# R202E.net
KiCad netlist of a schematic drawn in EAGLE
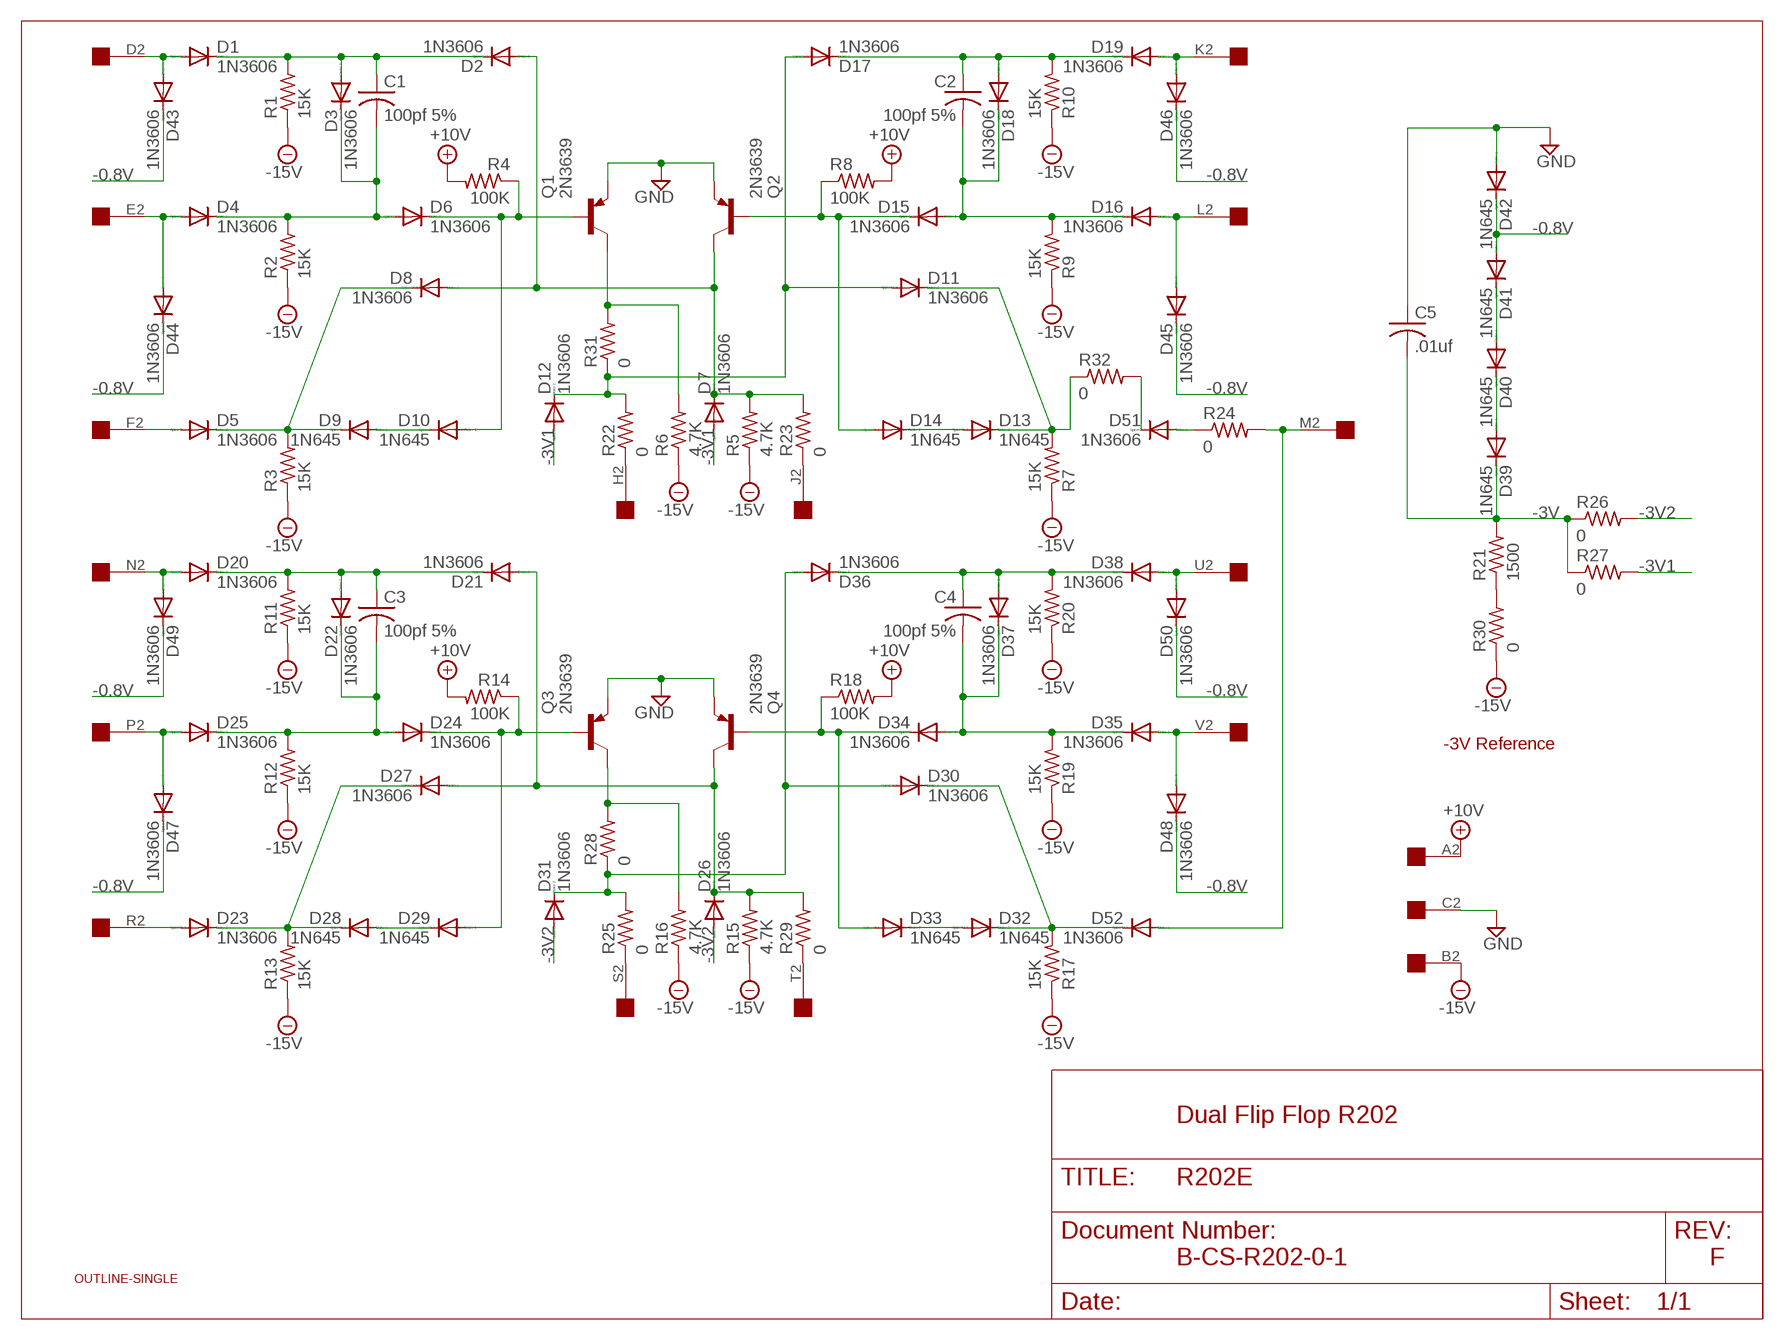
[diagram p0: schematic, sheet 1]

(export (version "E")
  (design (tool "Eeschema 10.0.6"))
  (components
    (comp (ref "C1")
      (value "100pf 5%")
      (footprint "eagle-import:C050-025X075")
      (libsource (lib "eagle-import") (part "C-US050-025X075"))
    )
    (comp (ref "C2")
      (value "100pf 5%")
      (footprint "eagle-import:C050-025X075")
      (libsource (lib "eagle-import") (part "C-US050-025X075"))
    )
    (comp (ref "C3")
      (value "100pf 5%")
      (footprint "eagle-import:C050-025X075")
      (libsource (lib "eagle-import") (part "C-US050-025X075"))
    )
    (comp (ref "C4")
      (value "100pf 5%")
      (footprint "eagle-import:C050-025X075")
      (libsource (lib "eagle-import") (part "C-US050-025X075"))
    )
    (comp (ref "C5")
      (value ".01uf")
      (footprint "eagle-import:C050-025X075")
      (libsource (lib "eagle-import") (part "C-US050-025X075"))
    )
    (comp (ref "D1")
      (value "1N3606")
      (footprint "eagle-import:DO35-10")
      (libsource (lib "eagle-import") (part "1N4148DO35-10"))
    )
    (comp (ref "D2")
      (value "1N3606")
      (footprint "eagle-import:DO35-10")
      (libsource (lib "eagle-import") (part "1N4148DO35-10"))
    )
    (comp (ref "D3")
      (value "1N3606")
      (footprint "eagle-import:DO35-10")
      (libsource (lib "eagle-import") (part "1N4148DO35-10"))
    )
    (comp (ref "D4")
      (value "1N3606")
      (footprint "eagle-import:DO35-10")
      (libsource (lib "eagle-import") (part "1N4148DO35-10"))
    )
    (comp (ref "D5")
      (value "1N3606")
      (footprint "eagle-import:DO35-10")
      (libsource (lib "eagle-import") (part "1N4148DO35-10"))
    )
    (comp (ref "D6")
      (value "1N3606")
      (footprint "eagle-import:DO35-10")
      (libsource (lib "eagle-import") (part "1N4148DO35-10"))
    )
    (comp (ref "D7")
      (value "1N3606")
      (footprint "eagle-import:DO35-10")
      (libsource (lib "eagle-import") (part "1N4148DO35-10"))
    )
    (comp (ref "D8")
      (value "1N3606")
      (footprint "eagle-import:DO35-10")
      (libsource (lib "eagle-import") (part "1N4148DO35-10"))
    )
    (comp (ref "D9")
      (value "1N645")
      (footprint "eagle-import:DO35-10")
      (libsource (lib "eagle-import") (part "1N4148DO35-10"))
    )
    (comp (ref "D10")
      (value "1N645")
      (footprint "eagle-import:DO35-10")
      (libsource (lib "eagle-import") (part "1N4148DO35-10"))
    )
    (comp (ref "D11")
      (value "1N3606")
      (footprint "eagle-import:DO35-10")
      (libsource (lib "eagle-import") (part "1N4148DO35-10"))
    )
    (comp (ref "D12")
      (value "1N3606")
      (footprint "eagle-import:DO35-10")
      (libsource (lib "eagle-import") (part "1N4148DO35-10"))
    )
    (comp (ref "D13")
      (value "1N645")
      (footprint "eagle-import:DO35-10")
      (libsource (lib "eagle-import") (part "1N4148DO35-10"))
    )
    (comp (ref "D14")
      (value "1N645")
      (footprint "eagle-import:DO35-10")
      (libsource (lib "eagle-import") (part "1N4148DO35-10"))
    )
    (comp (ref "D15")
      (value "1N3606")
      (footprint "eagle-import:DO35-10")
      (libsource (lib "eagle-import") (part "1N4148DO35-10"))
    )
    (comp (ref "D16")
      (value "1N3606")
      (footprint "eagle-import:DO35-10")
      (libsource (lib "eagle-import") (part "1N4148DO35-10"))
    )
    (comp (ref "D17")
      (value "1N3606")
      (footprint "eagle-import:DO35-10")
      (libsource (lib "eagle-import") (part "1N4148DO35-10"))
    )
    (comp (ref "D18")
      (value "1N3606")
      (footprint "eagle-import:DO35-10")
      (libsource (lib "eagle-import") (part "1N4148DO35-10"))
    )
    (comp (ref "D19")
      (value "1N3606")
      (footprint "eagle-import:DO35-10")
      (libsource (lib "eagle-import") (part "1N4148DO35-10"))
    )
    (comp (ref "D20")
      (value "1N3606")
      (footprint "eagle-import:DO35-10")
      (libsource (lib "eagle-import") (part "1N4148DO35-10"))
    )
    (comp (ref "D21")
      (value "1N3606")
      (footprint "eagle-import:DO35-10")
      (libsource (lib "eagle-import") (part "1N4148DO35-10"))
    )
    (comp (ref "D22")
      (value "1N3606")
      (footprint "eagle-import:DO35-10")
      (libsource (lib "eagle-import") (part "1N4148DO35-10"))
    )
    (comp (ref "D23")
      (value "1N3606")
      (footprint "eagle-import:DO35-10")
      (libsource (lib "eagle-import") (part "1N4148DO35-10"))
    )
    (comp (ref "D24")
      (value "1N3606")
      (footprint "eagle-import:DO35-10")
      (libsource (lib "eagle-import") (part "1N4148DO35-10"))
    )
    (comp (ref "D25")
      (value "1N3606")
      (footprint "eagle-import:DO35-10")
      (libsource (lib "eagle-import") (part "1N4148DO35-10"))
    )
    (comp (ref "D26")
      (value "1N3606")
      (footprint "eagle-import:DO35-10")
      (libsource (lib "eagle-import") (part "1N4148DO35-10"))
    )
    (comp (ref "D27")
      (value "1N3606")
      (footprint "eagle-import:DO35-10")
      (libsource (lib "eagle-import") (part "1N4148DO35-10"))
    )
    (comp (ref "D28")
      (value "1N645")
      (footprint "eagle-import:DO35-10")
      (libsource (lib "eagle-import") (part "1N4148DO35-10"))
    )
    (comp (ref "D29")
      (value "1N645")
      (footprint "eagle-import:DO35-10")
      (libsource (lib "eagle-import") (part "1N4148DO35-10"))
    )
    (comp (ref "D30")
      (value "1N3606")
      (footprint "eagle-import:DO35-10")
      (libsource (lib "eagle-import") (part "1N4148DO35-10"))
    )
    (comp (ref "D31")
      (value "1N3606")
      (footprint "eagle-import:DO35-10")
      (libsource (lib "eagle-import") (part "1N4148DO35-10"))
    )
    (comp (ref "D32")
      (value "1N645")
      (footprint "eagle-import:DO35-10")
      (libsource (lib "eagle-import") (part "1N4148DO35-10"))
    )
    (comp (ref "D33")
      (value "1N645")
      (footprint "eagle-import:DO35-10")
      (libsource (lib "eagle-import") (part "1N4148DO35-10"))
    )
    (comp (ref "D34")
      (value "1N3606")
      (footprint "eagle-import:DO35-10")
      (libsource (lib "eagle-import") (part "1N4148DO35-10"))
    )
    (comp (ref "D35")
      (value "1N3606")
      (footprint "eagle-import:DO35-10")
      (libsource (lib "eagle-import") (part "1N4148DO35-10"))
    )
    (comp (ref "D36")
      (value "1N3606")
      (footprint "eagle-import:DO35-10")
      (libsource (lib "eagle-import") (part "1N4148DO35-10"))
    )
    (comp (ref "D37")
      (value "1N3606")
      (footprint "eagle-import:DO35-10")
      (libsource (lib "eagle-import") (part "1N4148DO35-10"))
    )
    (comp (ref "D38")
      (value "1N3606")
      (footprint "eagle-import:DO35-10")
      (libsource (lib "eagle-import") (part "1N4148DO35-10"))
    )
    (comp (ref "D39")
      (value "1N645")
      (footprint "eagle-import:DO35-10")
      (libsource (lib "eagle-import") (part "1N4148DO35-10"))
    )
    (comp (ref "D40")
      (value "1N645")
      (footprint "eagle-import:DO35-10")
      (libsource (lib "eagle-import") (part "1N4148DO35-10"))
    )
    (comp (ref "D41")
      (value "1N645")
      (footprint "eagle-import:DO35-10")
      (libsource (lib "eagle-import") (part "1N4148DO35-10"))
    )
    (comp (ref "D42")
      (value "1N645")
      (footprint "eagle-import:DO35-10")
      (libsource (lib "eagle-import") (part "1N4148DO35-10"))
    )
    (comp (ref "D43")
      (value "1N3606")
      (footprint "eagle-import:DO35-10")
      (libsource (lib "eagle-import") (part "1N4148DO35-10"))
    )
    (comp (ref "D44")
      (value "1N3606")
      (footprint "eagle-import:DO35-10")
      (libsource (lib "eagle-import") (part "1N4148DO35-10"))
    )
    (comp (ref "D45")
      (value "1N3606")
      (footprint "eagle-import:DO35-10")
      (libsource (lib "eagle-import") (part "1N4148DO35-10"))
    )
    (comp (ref "D46")
      (value "1N3606")
      (footprint "eagle-import:DO35-10")
      (libsource (lib "eagle-import") (part "1N4148DO35-10"))
    )
    (comp (ref "D47")
      (value "1N3606")
      (footprint "eagle-import:DO35-10")
      (libsource (lib "eagle-import") (part "1N4148DO35-10"))
    )
    (comp (ref "D48")
      (value "1N3606")
      (footprint "eagle-import:DO35-10")
      (libsource (lib "eagle-import") (part "1N4148DO35-10"))
    )
    (comp (ref "D49")
      (value "1N3606")
      (footprint "eagle-import:DO35-10")
      (libsource (lib "eagle-import") (part "1N4148DO35-10"))
    )
    (comp (ref "D50")
      (value "1N3606")
      (footprint "eagle-import:DO35-10")
      (libsource (lib "eagle-import") (part "1N4148DO35-10"))
    )
    (comp (ref "D51")
      (value "1N3606")
      (footprint "eagle-import:DO35-10")
      (libsource (lib "eagle-import") (part "1N4148DO35-10"))
    )
    (comp (ref "D52")
      (value "1N3606")
      (footprint "eagle-import:DO35-10")
      (libsource (lib "eagle-import") (part "1N4148DO35-10"))
    )
    (comp (ref "Q1")
      (value "2N3639")
      (footprint "eagle-import:TO39")
      (libsource (lib "eagle-import") (part "2N3637"))
    )
    (comp (ref "Q2")
      (value "2N3639")
      (footprint "eagle-import:TO39")
      (libsource (lib "eagle-import") (part "2N3637"))
    )
    (comp (ref "Q3")
      (value "2N3639")
      (footprint "eagle-import:TO39")
      (libsource (lib "eagle-import") (part "2N3637"))
    )
    (comp (ref "Q4")
      (value "2N3639")
      (footprint "eagle-import:TO39")
      (libsource (lib "eagle-import") (part "2N3637"))
    )
    (comp (ref "R1")
      (value "15K")
      (footprint "eagle-import:0207_10")
      (libsource (lib "eagle-import") (part "R-US_0207/10"))
    )
    (comp (ref "R2")
      (value "15K")
      (footprint "eagle-import:0207_10")
      (libsource (lib "eagle-import") (part "R-US_0207/10"))
    )
    (comp (ref "R3")
      (value "15K")
      (footprint "eagle-import:0207_10")
      (libsource (lib "eagle-import") (part "R-US_0207/10"))
    )
    (comp (ref "R4")
      (value "100K")
      (footprint "eagle-import:0207_10")
      (libsource (lib "eagle-import") (part "R-US_0207/10"))
    )
    (comp (ref "R5")
      (value "4.7K")
      (footprint "eagle-import:0207_10")
      (libsource (lib "eagle-import") (part "R-US_0207/10"))
    )
    (comp (ref "R6")
      (value "4.7K")
      (footprint "eagle-import:0207_10")
      (libsource (lib "eagle-import") (part "R-US_0207/10"))
    )
    (comp (ref "R7")
      (value "15K")
      (footprint "eagle-import:0207_10")
      (libsource (lib "eagle-import") (part "R-US_0207/10"))
    )
    (comp (ref "R8")
      (value "100K")
      (footprint "eagle-import:0207_10")
      (libsource (lib "eagle-import") (part "R-US_0207/10"))
    )
    (comp (ref "R9")
      (value "15K")
      (footprint "eagle-import:0207_10")
      (libsource (lib "eagle-import") (part "R-US_0207/10"))
    )
    (comp (ref "R10")
      (value "15K")
      (footprint "eagle-import:0207_10")
      (libsource (lib "eagle-import") (part "R-US_0207/10"))
    )
    (comp (ref "R11")
      (value "15K")
      (footprint "eagle-import:0207_10")
      (libsource (lib "eagle-import") (part "R-US_0207/10"))
    )
    (comp (ref "R12")
      (value "15K")
      (footprint "eagle-import:0207_10")
      (libsource (lib "eagle-import") (part "R-US_0207/10"))
    )
    (comp (ref "R13")
      (value "15K")
      (footprint "eagle-import:0207_10")
      (libsource (lib "eagle-import") (part "R-US_0207/10"))
    )
    (comp (ref "R14")
      (value "100K")
      (footprint "eagle-import:0207_10")
      (libsource (lib "eagle-import") (part "R-US_0207/10"))
    )
    (comp (ref "R15")
      (value "4.7K")
      (footprint "eagle-import:0207_10")
      (libsource (lib "eagle-import") (part "R-US_0207/10"))
    )
    (comp (ref "R16")
      (value "4.7K")
      (footprint "eagle-import:0207_10")
      (libsource (lib "eagle-import") (part "R-US_0207/10"))
    )
    (comp (ref "R17")
      (value "15K")
      (footprint "eagle-import:0207_10")
      (libsource (lib "eagle-import") (part "R-US_0207/10"))
    )
    (comp (ref "R18")
      (value "100K")
      (footprint "eagle-import:0207_10")
      (libsource (lib "eagle-import") (part "R-US_0207/10"))
    )
    (comp (ref "R19")
      (value "15K")
      (footprint "eagle-import:0207_10")
      (libsource (lib "eagle-import") (part "R-US_0207/10"))
    )
    (comp (ref "R20")
      (value "15K")
      (footprint "eagle-import:0207_10")
      (libsource (lib "eagle-import") (part "R-US_0207/10"))
    )
    (comp (ref "R21")
      (value "1500")
      (footprint "eagle-import:0207_10")
      (libsource (lib "eagle-import") (part "R-US_0207/10"))
    )
    (comp (ref "R22")
      (value "0")
      (footprint "eagle-import:0207_10")
      (libsource (lib "eagle-import") (part "R-US_0207/10"))
    )
    (comp (ref "R23")
      (value "0")
      (footprint "eagle-import:0207_10")
      (libsource (lib "eagle-import") (part "R-US_0207/10"))
    )
    (comp (ref "R24")
      (value "0")
      (footprint "eagle-import:0207_10")
      (libsource (lib "eagle-import") (part "R-US_0207/10"))
    )
    (comp (ref "R25")
      (value "0")
      (footprint "eagle-import:0207_10")
      (libsource (lib "eagle-import") (part "R-US_0207/10"))
    )
    (comp (ref "R26")
      (value "0")
      (footprint "eagle-import:0207_10")
      (libsource (lib "eagle-import") (part "R-US_0207/10"))
    )
    (comp (ref "R27")
      (value "0")
      (footprint "eagle-import:0207_10")
      (libsource (lib "eagle-import") (part "R-US_0207/10"))
    )
    (comp (ref "R28")
      (value "0")
      (footprint "eagle-import:0207_10")
      (libsource (lib "eagle-import") (part "R-US_0207/10"))
    )
    (comp (ref "R29")
      (value "0")
      (footprint "eagle-import:0207_10")
      (libsource (lib "eagle-import") (part "R-US_0207/10"))
    )
    (comp (ref "R30")
      (value "0")
      (footprint "eagle-import:0207_10")
      (libsource (lib "eagle-import") (part "R-US_0207/10"))
    )
    (comp (ref "R31")
      (value "0")
      (footprint "eagle-import:0207_10")
      (libsource (lib "eagle-import") (part "R-US_0207/10"))
    )
    (comp (ref "R32")
      (value "0")
      (footprint "eagle-import:0207_10")
      (libsource (lib "eagle-import") (part "R-US_0207/10"))
    )
    (comp (ref "U$1")
      (value "OUTLINE-SINGLE")
      (footprint "eagle-import:SINGLE")
      (libsource (lib "eagle-import") (part "OUTLINE-SINGLE"))
    )
    (comp (ref "U$2")
      (value "EDGE-1")
      (footprint "eagle-import:EDGE-CON1")
      (libsource (lib "eagle-import") (part "EDGE-1"))
    )
  )
  (nets
    (net (code "1") (name "+10V") (class "Default")
      (node (ref "R14") (pin "2") (pinfunction "2_2") (pintype "passive"))
      (node (ref "R18") (pin "2") (pinfunction "2_2") (pintype "passive"))
      (node (ref "R4") (pin "2") (pinfunction "2_2") (pintype "passive"))
      (node (ref "R8") (pin "2") (pinfunction "2_2") (pintype "passive"))
      (node (ref "U$2") (pin "A2") (pinfunction "1_A2") (pintype "bidirectional"))
    )
    (net (code "2") (name "-15V") (class "Default")
      (node (ref "R1") (pin "1") (pinfunction "1_1") (pintype "passive"))
      (node (ref "R10") (pin "1") (pinfunction "1_1") (pintype "passive"))
      (node (ref "R11") (pin "1") (pinfunction "1_1") (pintype "passive"))
      (node (ref "R12") (pin "1") (pinfunction "1_1") (pintype "passive"))
      (node (ref "R13") (pin "1") (pinfunction "1_1") (pintype "passive"))
      (node (ref "R15") (pin "1") (pinfunction "1_1") (pintype "passive"))
      (node (ref "R16") (pin "1") (pinfunction "1_1") (pintype "passive"))
      (node (ref "R17") (pin "1") (pinfunction "1_1") (pintype "passive"))
      (node (ref "R19") (pin "1") (pinfunction "1_1") (pintype "passive"))
      (node (ref "R2") (pin "1") (pinfunction "1_1") (pintype "passive"))
      (node (ref "R20") (pin "1") (pinfunction "1_1") (pintype "passive"))
      (node (ref "R3") (pin "1") (pinfunction "1_1") (pintype "passive"))
      (node (ref "R30") (pin "1") (pinfunction "1_1") (pintype "passive"))
      (node (ref "R5") (pin "1") (pinfunction "1_1") (pintype "passive"))
      (node (ref "R6") (pin "1") (pinfunction "1_1") (pintype "passive"))
      (node (ref "R7") (pin "1") (pinfunction "1_1") (pintype "passive"))
      (node (ref "R9") (pin "1") (pinfunction "1_1") (pintype "passive"))
      (node (ref "U$2") (pin "B2") (pinfunction "1_B2") (pintype "bidirectional"))
    )
    (net (code "3") (name "/-0.8V") (class "Default")
      (node (ref "D41") (pin "A") (pinfunction "A_A") (pintype "passive"))
      (node (ref "D42") (pin "C") (pinfunction "C_C") (pintype "passive"))
      (node (ref "D43") (pin "C") (pinfunction "C_C") (pintype "passive"))
      (node (ref "D44") (pin "C") (pinfunction "C_C") (pintype "passive"))
      (node (ref "D45") (pin "C") (pinfunction "C_C") (pintype "passive"))
      (node (ref "D46") (pin "C") (pinfunction "C_C") (pintype "passive"))
      (node (ref "D47") (pin "C") (pinfunction "C_C") (pintype "passive"))
      (node (ref "D48") (pin "C") (pinfunction "C_C") (pintype "passive"))
      (node (ref "D49") (pin "C") (pinfunction "C_C") (pintype "passive"))
      (node (ref "D50") (pin "C") (pinfunction "C_C") (pintype "passive"))
    )
    (net (code "4") (name "/-3V") (class "Default")
      (node (ref "C5") (pin "2") (pinfunction "2_2") (pintype "passive"))
      (node (ref "D39") (pin "C") (pinfunction "C_C") (pintype "passive"))
      (node (ref "R21") (pin "2") (pinfunction "2_2") (pintype "passive"))
      (node (ref "R26") (pin "1") (pinfunction "1_1") (pintype "passive"))
      (node (ref "R27") (pin "1") (pinfunction "1_1") (pintype "passive"))
    )
    (net (code "5") (name "/-3V1") (class "Default")
      (node (ref "D12") (pin "A") (pinfunction "A_A") (pintype "passive"))
      (node (ref "D7") (pin "A") (pinfunction "A_A") (pintype "passive"))
      (node (ref "R27") (pin "2") (pinfunction "2_2") (pintype "passive"))
    )
    (net (code "6") (name "/-3V2") (class "Default")
      (node (ref "D26") (pin "A") (pinfunction "A_A") (pintype "passive"))
      (node (ref "D31") (pin "A") (pinfunction "A_A") (pintype "passive"))
      (node (ref "R26") (pin "2") (pinfunction "2_2") (pintype "passive"))
    )
    (net (code "7") (name "GND") (class "Default")
      (node (ref "C5") (pin "1") (pinfunction "1_1") (pintype "passive"))
      (node (ref "D42") (pin "A") (pinfunction "A_A") (pintype "passive"))
      (node (ref "Q1") (pin "1") (pinfunction "E_1") (pintype "passive"))
      (node (ref "Q2") (pin "1") (pinfunction "E_1") (pintype "passive"))
      (node (ref "Q3") (pin "1") (pinfunction "E_1") (pintype "passive"))
      (node (ref "Q4") (pin "1") (pinfunction "E_1") (pintype "passive"))
      (node (ref "U$2") (pin "C2") (pinfunction "1_C2") (pintype "bidirectional"))
    )
    (net (code "8") (name "Net-(C1-Pad1)") (class "Default")
      (node (ref "C1") (pin "1") (pinfunction "1_1") (pintype "passive"))
      (node (ref "D1") (pin "C") (pinfunction "C_C") (pintype "passive"))
      (node (ref "D2") (pin "C") (pinfunction "C_C") (pintype "passive"))
      (node (ref "D3") (pin "A") (pinfunction "A_A") (pintype "passive"))
      (node (ref "R1") (pin "2") (pinfunction "2_2") (pintype "passive"))
    )
    (net (code "9") (name "Net-(C1-Pad2)") (class "Default")
      (node (ref "C1") (pin "2") (pinfunction "2_2") (pintype "passive"))
      (node (ref "D3") (pin "C") (pinfunction "C_C") (pintype "passive"))
      (node (ref "D4") (pin "C") (pinfunction "C_C") (pintype "passive"))
      (node (ref "D6") (pin "A") (pinfunction "A_A") (pintype "passive"))
      (node (ref "R2") (pin "2") (pinfunction "2_2") (pintype "passive"))
    )
    (net (code "10") (name "Net-(C2-Pad1)") (class "Default")
      (node (ref "C2") (pin "1") (pinfunction "1_1") (pintype "passive"))
      (node (ref "D17") (pin "C") (pinfunction "C_C") (pintype "passive"))
      (node (ref "D18") (pin "A") (pinfunction "A_A") (pintype "passive"))
      (node (ref "D19") (pin "C") (pinfunction "C_C") (pintype "passive"))
      (node (ref "R10") (pin "2") (pinfunction "2_2") (pintype "passive"))
    )
    (net (code "11") (name "Net-(C2-Pad2)") (class "Default")
      (node (ref "C2") (pin "2") (pinfunction "2_2") (pintype "passive"))
      (node (ref "D15") (pin "A") (pinfunction "A_A") (pintype "passive"))
      (node (ref "D16") (pin "C") (pinfunction "C_C") (pintype "passive"))
      (node (ref "D18") (pin "C") (pinfunction "C_C") (pintype "passive"))
      (node (ref "R9") (pin "2") (pinfunction "2_2") (pintype "passive"))
    )
    (net (code "12") (name "Net-(C3-Pad1)") (class "Default")
      (node (ref "C3") (pin "1") (pinfunction "1_1") (pintype "passive"))
      (node (ref "D20") (pin "C") (pinfunction "C_C") (pintype "passive"))
      (node (ref "D21") (pin "C") (pinfunction "C_C") (pintype "passive"))
      (node (ref "D22") (pin "A") (pinfunction "A_A") (pintype "passive"))
      (node (ref "R11") (pin "2") (pinfunction "2_2") (pintype "passive"))
    )
    (net (code "13") (name "Net-(C3-Pad2)") (class "Default")
      (node (ref "C3") (pin "2") (pinfunction "2_2") (pintype "passive"))
      (node (ref "D22") (pin "C") (pinfunction "C_C") (pintype "passive"))
      (node (ref "D24") (pin "A") (pinfunction "A_A") (pintype "passive"))
      (node (ref "D25") (pin "C") (pinfunction "C_C") (pintype "passive"))
      (node (ref "R12") (pin "2") (pinfunction "2_2") (pintype "passive"))
    )
    (net (code "14") (name "Net-(C4-Pad1)") (class "Default")
      (node (ref "C4") (pin "1") (pinfunction "1_1") (pintype "passive"))
      (node (ref "D36") (pin "C") (pinfunction "C_C") (pintype "passive"))
      (node (ref "D37") (pin "A") (pinfunction "A_A") (pintype "passive"))
      (node (ref "D38") (pin "C") (pinfunction "C_C") (pintype "passive"))
      (node (ref "R20") (pin "2") (pinfunction "2_2") (pintype "passive"))
    )
    (net (code "15") (name "Net-(C4-Pad2)") (class "Default")
      (node (ref "C4") (pin "2") (pinfunction "2_2") (pintype "passive"))
      (node (ref "D34") (pin "A") (pinfunction "A_A") (pintype "passive"))
      (node (ref "D35") (pin "C") (pinfunction "C_C") (pintype "passive"))
      (node (ref "D37") (pin "C") (pinfunction "C_C") (pintype "passive"))
      (node (ref "R19") (pin "2") (pinfunction "2_2") (pintype "passive"))
    )
    (net (code "16") (name "Net-(D5-PadC)") (class "Default")
      (node (ref "D5") (pin "C") (pinfunction "C_C") (pintype "passive"))
      (node (ref "D8") (pin "C") (pinfunction "C_C") (pintype "passive"))
      (node (ref "D9") (pin "C") (pinfunction "C_C") (pintype "passive"))
      (node (ref "R3") (pin "2") (pinfunction "2_2") (pintype "passive"))
    )
    (net (code "17") (name "Net-(D10-PadC)") (class "Default")
      (node (ref "D10") (pin "C") (pinfunction "C_C") (pintype "passive"))
      (node (ref "D9") (pin "A") (pinfunction "A_A") (pintype "passive"))
    )
    (net (code "18") (name "Net-(D11-PadA)") (class "Default")
      (node (ref "D11") (pin "A") (pinfunction "A_A") (pintype "passive"))
      (node (ref "D12") (pin "C") (pinfunction "C_C") (pintype "passive"))
      (node (ref "D17") (pin "A") (pinfunction "A_A") (pintype "passive"))
      (node (ref "R22") (pin "2") (pinfunction "2_2") (pintype "passive"))
      (node (ref "R31") (pin "1") (pinfunction "1_1") (pintype "passive"))
    )
    (net (code "19") (name "Net-(D11-PadC)") (class "Default")
      (node (ref "D11") (pin "C") (pinfunction "C_C") (pintype "passive"))
      (node (ref "D13") (pin "C") (pinfunction "C_C") (pintype "passive"))
      (node (ref "R32") (pin "1") (pinfunction "1_1") (pintype "passive"))
      (node (ref "R7") (pin "2") (pinfunction "2_2") (pintype "passive"))
    )
    (net (code "20") (name "Net-(D13-PadA)") (class "Default")
      (node (ref "D13") (pin "A") (pinfunction "A_A") (pintype "passive"))
      (node (ref "D14") (pin "C") (pinfunction "C_C") (pintype "passive"))
    )
    (net (code "21") (name "Net-(D23-PadC)") (class "Default")
      (node (ref "D23") (pin "C") (pinfunction "C_C") (pintype "passive"))
      (node (ref "D27") (pin "C") (pinfunction "C_C") (pintype "passive"))
      (node (ref "D28") (pin "C") (pinfunction "C_C") (pintype "passive"))
      (node (ref "R13") (pin "2") (pinfunction "2_2") (pintype "passive"))
    )
    (net (code "22") (name "Net-(D28-PadA)") (class "Default")
      (node (ref "D28") (pin "A") (pinfunction "A_A") (pintype "passive"))
      (node (ref "D29") (pin "C") (pinfunction "C_C") (pintype "passive"))
    )
    (net (code "23") (name "Net-(D30-PadA)") (class "Default")
      (node (ref "D30") (pin "A") (pinfunction "A_A") (pintype "passive"))
      (node (ref "D31") (pin "C") (pinfunction "C_C") (pintype "passive"))
      (node (ref "D36") (pin "A") (pinfunction "A_A") (pintype "passive"))
      (node (ref "R25") (pin "2") (pinfunction "2_2") (pintype "passive"))
      (node (ref "R28") (pin "1") (pinfunction "1_1") (pintype "passive"))
    )
    (net (code "24") (name "Net-(D30-PadC)") (class "Default")
      (node (ref "D30") (pin "C") (pinfunction "C_C") (pintype "passive"))
      (node (ref "D32") (pin "C") (pinfunction "C_C") (pintype "passive"))
      (node (ref "D52") (pin "C") (pinfunction "C_C") (pintype "passive"))
      (node (ref "R17") (pin "2") (pinfunction "2_2") (pintype "passive"))
    )
    (net (code "25") (name "Net-(D32-PadA)") (class "Default")
      (node (ref "D32") (pin "A") (pinfunction "A_A") (pintype "passive"))
      (node (ref "D33") (pin "C") (pinfunction "C_C") (pintype "passive"))
    )
    (net (code "26") (name "Net-(D39-PadA)") (class "Default")
      (node (ref "D39") (pin "A") (pinfunction "A_A") (pintype "passive"))
      (node (ref "D40") (pin "C") (pinfunction "C_C") (pintype "passive"))
    )
    (net (code "27") (name "Net-(D40-PadA)") (class "Default")
      (node (ref "D40") (pin "A") (pinfunction "A_A") (pintype "passive"))
      (node (ref "D41") (pin "C") (pinfunction "C_C") (pintype "passive"))
    )
    (net (code "28") (name "Net-(D51-PadA)") (class "Default")
      (node (ref "D51") (pin "A") (pinfunction "A_A") (pintype "passive"))
      (node (ref "R24") (pin "1") (pinfunction "1_1") (pintype "passive"))
    )
    (net (code "29") (name "Net-(D51-PadC)") (class "Default")
      (node (ref "D51") (pin "C") (pinfunction "C_C") (pintype "passive"))
      (node (ref "R32") (pin "2") (pinfunction "2_2") (pintype "passive"))
    )
    (net (code "30") (name "Net-(Q1-B)") (class "Default")
      (node (ref "D10") (pin "A") (pinfunction "A_A") (pintype "passive"))
      (node (ref "D6") (pin "C") (pinfunction "C_C") (pintype "passive"))
      (node (ref "Q1") (pin "2") (pinfunction "B_2") (pintype "passive"))
      (node (ref "R4") (pin "1") (pinfunction "1_1") (pintype "passive"))
    )
    (net (code "31") (name "Net-(Q1-C)") (class "Default")
      (node (ref "Q1") (pin "3") (pinfunction "C_3") (pintype "passive"))
      (node (ref "R31") (pin "2") (pinfunction "2_2") (pintype "passive"))
      (node (ref "R6") (pin "2") (pinfunction "2_2") (pintype "passive"))
    )
    (net (code "32") (name "Net-(Q2-B)") (class "Default")
      (node (ref "D14") (pin "A") (pinfunction "A_A") (pintype "passive"))
      (node (ref "D15") (pin "C") (pinfunction "C_C") (pintype "passive"))
      (node (ref "Q2") (pin "2") (pinfunction "B_2") (pintype "passive"))
      (node (ref "R8") (pin "1") (pinfunction "1_1") (pintype "passive"))
    )
    (net (code "33") (name "Net-(Q2-C)") (class "Default")
      (node (ref "D2") (pin "A") (pinfunction "A_A") (pintype "passive"))
      (node (ref "D7") (pin "C") (pinfunction "C_C") (pintype "passive"))
      (node (ref "D8") (pin "A") (pinfunction "A_A") (pintype "passive"))
      (node (ref "Q2") (pin "3") (pinfunction "C_3") (pintype "passive"))
      (node (ref "R23") (pin "2") (pinfunction "2_2") (pintype "passive"))
      (node (ref "R5") (pin "2") (pinfunction "2_2") (pintype "passive"))
    )
    (net (code "34") (name "Net-(Q3-B)") (class "Default")
      (node (ref "D24") (pin "C") (pinfunction "C_C") (pintype "passive"))
      (node (ref "D29") (pin "A") (pinfunction "A_A") (pintype "passive"))
      (node (ref "Q3") (pin "2") (pinfunction "B_2") (pintype "passive"))
      (node (ref "R14") (pin "1") (pinfunction "1_1") (pintype "passive"))
    )
    (net (code "35") (name "Net-(Q3-C)") (class "Default")
      (node (ref "Q3") (pin "3") (pinfunction "C_3") (pintype "passive"))
      (node (ref "R16") (pin "2") (pinfunction "2_2") (pintype "passive"))
      (node (ref "R28") (pin "2") (pinfunction "2_2") (pintype "passive"))
    )
    (net (code "36") (name "Net-(Q4-B)") (class "Default")
      (node (ref "D33") (pin "A") (pinfunction "A_A") (pintype "passive"))
      (node (ref "D34") (pin "C") (pinfunction "C_C") (pintype "passive"))
      (node (ref "Q4") (pin "2") (pinfunction "B_2") (pintype "passive"))
      (node (ref "R18") (pin "1") (pinfunction "1_1") (pintype "passive"))
    )
    (net (code "37") (name "Net-(Q4-C)") (class "Default")
      (node (ref "D21") (pin "A") (pinfunction "A_A") (pintype "passive"))
      (node (ref "D26") (pin "C") (pinfunction "C_C") (pintype "passive"))
      (node (ref "D27") (pin "A") (pinfunction "A_A") (pintype "passive"))
      (node (ref "Q4") (pin "3") (pinfunction "C_3") (pintype "passive"))
      (node (ref "R15") (pin "2") (pinfunction "2_2") (pintype "passive"))
      (node (ref "R29") (pin "2") (pinfunction "2_2") (pintype "passive"))
    )
    (net (code "38") (name "Net-(R21-Pad1)") (class "Default")
      (node (ref "R21") (pin "1") (pinfunction "1_1") (pintype "passive"))
      (node (ref "R30") (pin "2") (pinfunction "2_2") (pintype "passive"))
    )
    (net (code "39") (name "Net-(U$2D-1)") (class "Default")
      (node (ref "D1") (pin "A") (pinfunction "A_A") (pintype "passive"))
      (node (ref "D43") (pin "A") (pinfunction "A_A") (pintype "passive"))
      (node (ref "U$2") (pin "D2") (pinfunction "1_D2") (pintype "bidirectional"))
    )
    (net (code "40") (name "Net-(U$2E-1)") (class "Default")
      (node (ref "D4") (pin "A") (pinfunction "A_A") (pintype "passive"))
      (node (ref "D44") (pin "A") (pinfunction "A_A") (pintype "passive"))
      (node (ref "U$2") (pin "E2") (pinfunction "1_E2") (pintype "bidirectional"))
    )
    (net (code "41") (name "Net-(U$2F-1)") (class "Default")
      (node (ref "D5") (pin "A") (pinfunction "A_A") (pintype "passive"))
      (node (ref "U$2") (pin "F2") (pinfunction "1_F2") (pintype "bidirectional"))
    )
    (net (code "42") (name "Net-(U$2G-1)") (class "Default")
      (node (ref "R22") (pin "1") (pinfunction "1_1") (pintype "passive"))
      (node (ref "U$2") (pin "H2") (pinfunction "1_H2") (pintype "bidirectional"))
    )
    (net (code "43") (name "Net-(U$2H-1)") (class "Default")
      (node (ref "R23") (pin "1") (pinfunction "1_1") (pintype "passive"))
      (node (ref "U$2") (pin "J2") (pinfunction "1_J2") (pintype "bidirectional"))
    )
    (net (code "44") (name "Net-(U$2I-1)") (class "Default")
      (node (ref "D19") (pin "A") (pinfunction "A_A") (pintype "passive"))
      (node (ref "D46") (pin "A") (pinfunction "A_A") (pintype "passive"))
      (node (ref "U$2") (pin "K2") (pinfunction "1_K2") (pintype "bidirectional"))
    )
    (net (code "45") (name "Net-(U$2J-1)") (class "Default")
      (node (ref "D16") (pin "A") (pinfunction "A_A") (pintype "passive"))
      (node (ref "D45") (pin "A") (pinfunction "A_A") (pintype "passive"))
      (node (ref "U$2") (pin "L2") (pinfunction "1_L2") (pintype "bidirectional"))
    )
    (net (code "46") (name "Net-(U$2K-1)") (class "Default")
      (node (ref "D52") (pin "A") (pinfunction "A_A") (pintype "passive"))
      (node (ref "R24") (pin "2") (pinfunction "2_2") (pintype "passive"))
      (node (ref "U$2") (pin "M2") (pinfunction "1_M2") (pintype "bidirectional"))
    )
    (net (code "47") (name "Net-(U$2L-1)") (class "Default")
      (node (ref "D20") (pin "A") (pinfunction "A_A") (pintype "passive"))
      (node (ref "D49") (pin "A") (pinfunction "A_A") (pintype "passive"))
      (node (ref "U$2") (pin "N2") (pinfunction "1_N2") (pintype "bidirectional"))
    )
    (net (code "48") (name "Net-(U$2M-1)") (class "Default")
      (node (ref "D25") (pin "A") (pinfunction "A_A") (pintype "passive"))
      (node (ref "D47") (pin "A") (pinfunction "A_A") (pintype "passive"))
      (node (ref "U$2") (pin "P2") (pinfunction "1_P2") (pintype "bidirectional"))
    )
    (net (code "49") (name "Net-(U$2N-1)") (class "Default")
      (node (ref "D23") (pin "A") (pinfunction "A_A") (pintype "passive"))
      (node (ref "U$2") (pin "R2") (pinfunction "1_R2") (pintype "bidirectional"))
    )
    (net (code "50") (name "Net-(U$2O-1)") (class "Default")
      (node (ref "R25") (pin "1") (pinfunction "1_1") (pintype "passive"))
      (node (ref "U$2") (pin "S2") (pinfunction "1_S2") (pintype "bidirectional"))
    )
    (net (code "51") (name "Net-(U$2P-1)") (class "Default")
      (node (ref "R29") (pin "1") (pinfunction "1_1") (pintype "passive"))
      (node (ref "U$2") (pin "T2") (pinfunction "1_T2") (pintype "bidirectional"))
    )
    (net (code "52") (name "Net-(U$2Q-1)") (class "Default")
      (node (ref "D38") (pin "A") (pinfunction "A_A") (pintype "passive"))
      (node (ref "D50") (pin "A") (pinfunction "A_A") (pintype "passive"))
      (node (ref "U$2") (pin "U2") (pinfunction "1_U2") (pintype "bidirectional"))
    )
    (net (code "53") (name "Net-(U$2R-1)") (class "Default")
      (node (ref "D35") (pin "A") (pinfunction "A_A") (pintype "passive"))
      (node (ref "D48") (pin "A") (pinfunction "A_A") (pintype "passive"))
      (node (ref "U$2") (pin "V2") (pinfunction "1_V2") (pintype "bidirectional"))
    )
  )
)
